# generic_maxi_speed_1.net
KiCad netlist of a schematic drawn in EAGLE
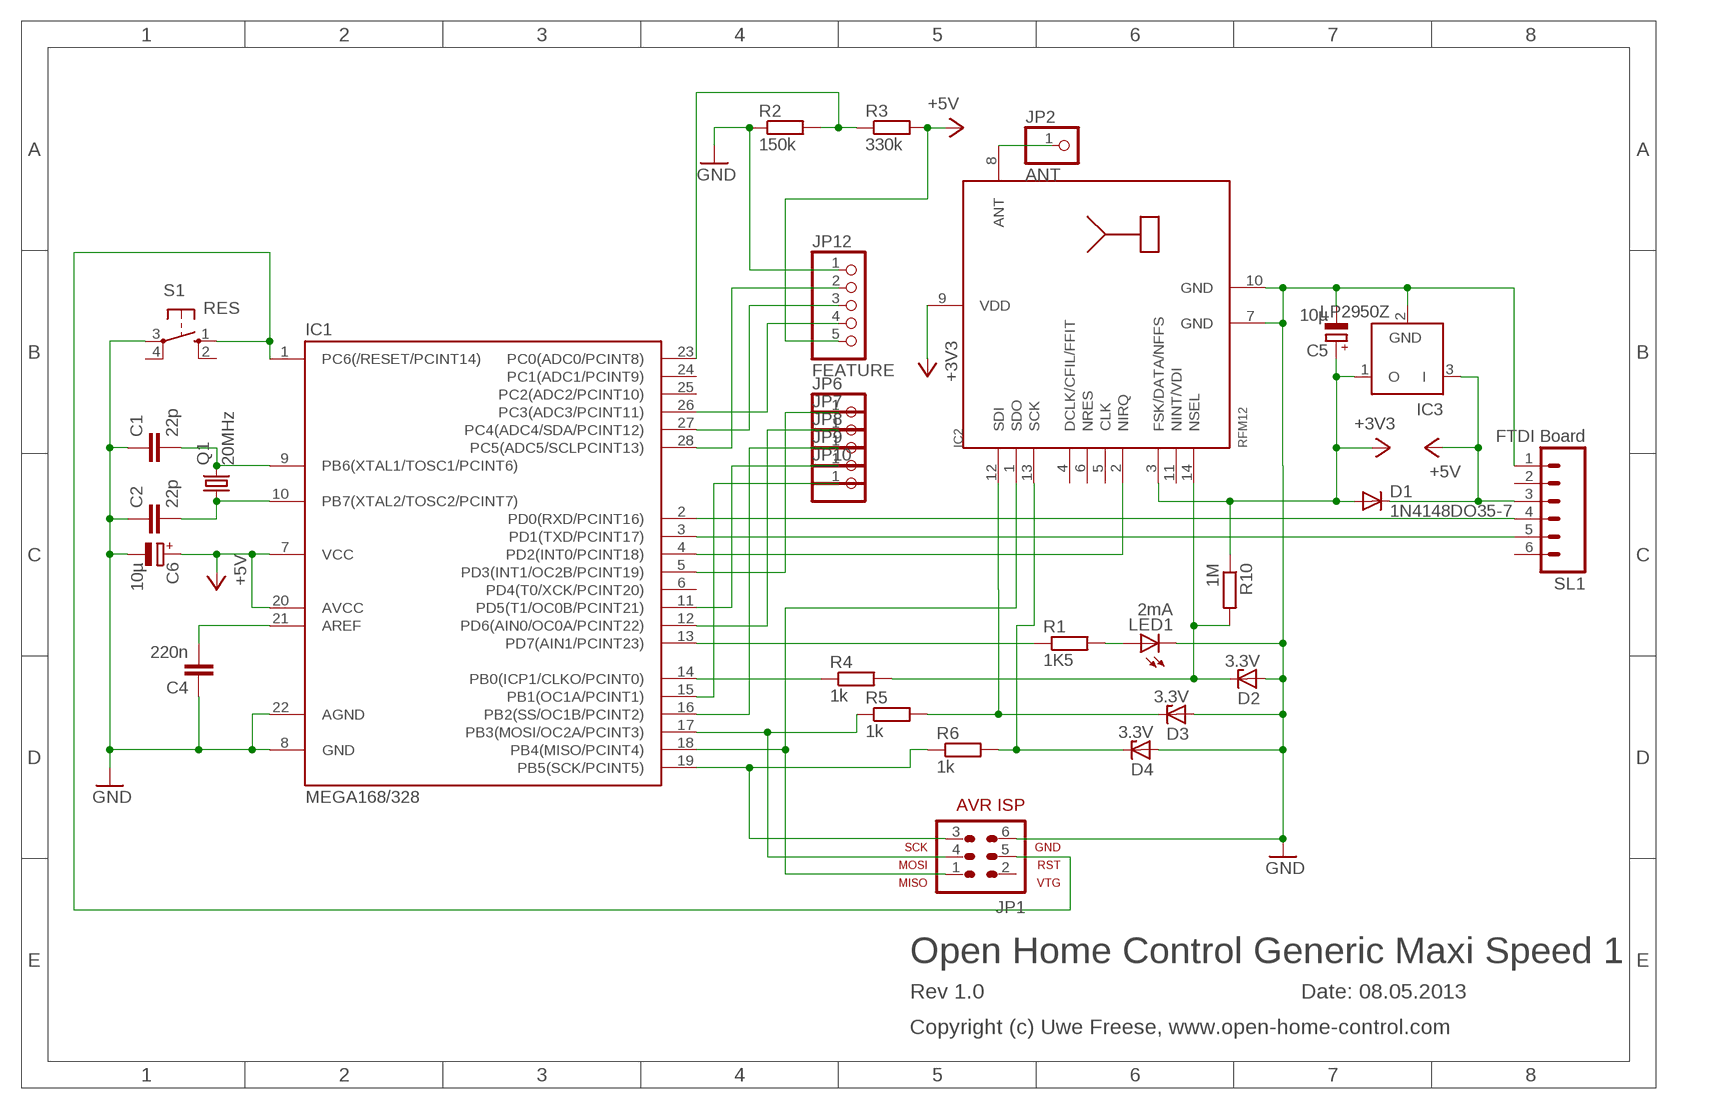
[diagram p0: schematic, sheet 1]

(export (version "E")
  (design (tool "Eeschema 10.0.6"))
  (components
    (comp (ref "C1")
      (value "22p")
      (footprint "eagle-import:C025-024X044")
      (libsource (lib "eagle-import") (part "C-EU025-024X044"))
    )
    (comp (ref "C2")
      (value "22p")
      (footprint "eagle-import:C025-024X044")
      (libsource (lib "eagle-import") (part "C-EU025-024X044"))
    )
    (comp (ref "C4")
      (value "220n")
      (footprint "eagle-import:C025-030X050")
      (libsource (lib "eagle-import") (part "C-EU025-030X050"))
    )
    (comp (ref "C5")
      (value "10µ")
      (footprint "eagle-import:E1,8-4")
      (libsource (lib "eagle-import") (part "CPOL-EUE1.8-4"))
    )
    (comp (ref "C6")
      (value "10µ")
      (footprint "eagle-import:E1,8-4")
      (libsource (lib "eagle-import") (part "CPOL-EUE1.8-4"))
    )
    (comp (ref "D1")
      (value "1N4148DO35-7")
      (footprint "eagle-import:DO35-7")
      (libsource (lib "eagle-import") (part "1N4148DO35-7"))
    )
    (comp (ref "D2")
      (value "3.3V")
      (footprint "eagle-import:ZDIO-5")
      (libsource (lib "eagle-import") (part "ZENER-DIODEZD-5"))
    )
    (comp (ref "D3")
      (value "3.3V")
      (footprint "eagle-import:ZDIO-5")
      (libsource (lib "eagle-import") (part "ZENER-DIODEZD-5"))
    )
    (comp (ref "D4")
      (value "3.3V")
      (footprint "eagle-import:ZDIO-5")
      (libsource (lib "eagle-import") (part "ZENER-DIODEZD-5"))
    )
    (comp (ref "IC1")
      (value "MEGA168/328")
      (footprint "eagle-import:DIL28-3")
      (libsource (lib "eagle-import") (part "MEGA48/88/168-PU"))
    )
    (comp (ref "IC2")
      (value "RFM12")
      (footprint "eagle-import:RFM")
      (libsource (lib "eagle-import") (part "RFM12"))
    )
    (comp (ref "IC3")
      (value "LP2950Z")
      (footprint "eagle-import:TO92")
      (libsource (lib "eagle-import") (part "LP2950Z"))
    )
    (comp (ref "JP1")
      (value "AVR-ISP-6")
      (footprint "eagle-import:AVR-ISP-6")
      (libsource (lib "eagle-import") (part "AVR-ISP-6"))
    )
    (comp (ref "JP2")
      (value "ANT")
      (footprint "eagle-import:1X01")
      (libsource (lib "eagle-import") (part "PINHD-1X1"))
    )
    (comp (ref "JP6")
      (value "PINHD-1X1")
      (footprint "eagle-import:1X01")
      (libsource (lib "eagle-import") (part "PINHD-1X1"))
    )
    (comp (ref "JP7")
      (value "PINHD-1X1")
      (footprint "eagle-import:1X01")
      (libsource (lib "eagle-import") (part "PINHD-1X1"))
    )
    (comp (ref "JP8")
      (value "PINHD-1X1")
      (footprint "eagle-import:1X01")
      (libsource (lib "eagle-import") (part "PINHD-1X1"))
    )
    (comp (ref "JP9")
      (value "PINHD-1X1")
      (footprint "eagle-import:1X01")
      (libsource (lib "eagle-import") (part "PINHD-1X1"))
    )
    (comp (ref "JP10")
      (value "PINHD-1X1")
      (footprint "eagle-import:1X01")
      (libsource (lib "eagle-import") (part "PINHD-1X1"))
    )
    (comp (ref "JP12")
      (value "FEATURE")
      (footprint "eagle-import:1X05")
      (libsource (lib "eagle-import") (part "PINHD-1X5"))
    )
    (comp (ref "LED1")
      (value "2mA")
      (footprint "eagle-import:LED3MM")
      (libsource (lib "eagle-import") (part "LED3MM"))
    )
    (comp (ref "Q1")
      (value "20MHz")
      (footprint "eagle-import:HC49_S")
      (libsource (lib "eagle-import") (part "CRYSTALHC49S"))
    )
    (comp (ref "R1")
      (value "1K5")
      (footprint "eagle-import:0207_7")
      (libsource (lib "eagle-import") (part "R-EU_0207/7"))
    )
    (comp (ref "R2")
      (value "150k")
      (footprint "eagle-import:0207_7")
      (libsource (lib "eagle-import") (part "R-EU_0207/7"))
    )
    (comp (ref "R3")
      (value "330k")
      (footprint "eagle-import:0207_7")
      (libsource (lib "eagle-import") (part "R-EU_0207/7"))
    )
    (comp (ref "R4")
      (value "1k")
      (footprint "eagle-import:0207_7")
      (libsource (lib "eagle-import") (part "R-EU_0207/7"))
    )
    (comp (ref "R5")
      (value "1k")
      (footprint "eagle-import:0207_7")
      (libsource (lib "eagle-import") (part "R-EU_0207/7"))
    )
    (comp (ref "R6")
      (value "1k")
      (footprint "eagle-import:0207_7")
      (libsource (lib "eagle-import") (part "R-EU_0207/7"))
    )
    (comp (ref "R10")
      (value "1M")
      (footprint "eagle-import:0207_7")
      (libsource (lib "eagle-import") (part "R-EU_0207/7"))
    )
    (comp (ref "S1")
      (value "RES")
      (footprint "eagle-import:B3F-10XX")
      (fields (field (name "MPN") "B3F-1000"))
      (libsource (lib "eagle-import") (part "10-XX"))
    )
    (comp (ref "SL1")
      (value "FTDI Board")
      (footprint "eagle-import:06P")
      (libsource (lib "eagle-import") (part "M06"))
    )
  )
  (nets
    (net (code "1") (name "+3V3") (class "Default")
      (node (ref "C5") (pin "+") (pinfunction "+_+") (pintype "passive"))
      (node (ref "D1") (pin "A") (pinfunction "A_A") (pintype "passive"))
      (node (ref "IC2") (pin "3") (pinfunction "FSK/DATA/NFFS_3") (pintype "bidirectional"))
      (node (ref "IC2") (pin "9") (pinfunction "VDD_9") (pintype "power_in"))
      (node (ref "IC3") (pin "1") (pinfunction "O_1") (pintype "input"))
      (node (ref "R10") (pin "1") (pinfunction "1_1") (pintype "passive"))
    )
    (net (code "2") (name "+5V") (class "Default")
      (node (ref "C6") (pin "+") (pinfunction "+_+") (pintype "passive"))
      (node (ref "D1") (pin "C") (pinfunction "C_C") (pintype "passive"))
      (node (ref "IC1") (pin "20") (pinfunction "AVCC_20") (pintype "passive"))
      (node (ref "IC1") (pin "7") (pinfunction "VCC_7") (pintype "power_in"))
      (node (ref "IC3") (pin "3") (pinfunction "I_3") (pintype "input"))
      (node (ref "JP12") (pin "5") (pinfunction "5_5") (pintype "passive"))
      (node (ref "R3") (pin "2") (pinfunction "2_2") (pintype "passive"))
      (node (ref "SL1") (pin "3") (pinfunction "3_3") (pintype "passive"))
    )
    (net (code "3") (name "GND") (class "Default")
      (node (ref "C1") (pin "1") (pinfunction "1_1") (pintype "passive"))
      (node (ref "C2") (pin "1") (pinfunction "1_1") (pintype "passive"))
      (node (ref "C4") (pin "1") (pinfunction "1_1") (pintype "passive"))
      (node (ref "C5") (pin "-") (pinfunction "-_-") (pintype "passive"))
      (node (ref "C6") (pin "-") (pinfunction "-_-") (pintype "passive"))
      (node (ref "D2") (pin "A") (pinfunction "A_A") (pintype "passive"))
      (node (ref "D3") (pin "A") (pinfunction "A_A") (pintype "passive"))
      (node (ref "D4") (pin "A") (pinfunction "A_A") (pintype "passive"))
      (node (ref "IC1") (pin "22") (pinfunction "AGND_22") (pintype "power_in"))
      (node (ref "IC1") (pin "8") (pinfunction "GND_8") (pintype "power_in"))
      (node (ref "IC2") (pin "10") (pinfunction "GND_10") (pintype "power_in"))
      (node (ref "IC2") (pin "7") (pinfunction "GND_7") (pintype "power_in"))
      (node (ref "IC3") (pin "2") (pinfunction "GND_2") (pintype "power_in"))
      (node (ref "JP1") (pin "6") (pinfunction "6_6") (pintype "passive"))
      (node (ref "JP12") (pin "1") (pinfunction "1_1") (pintype "passive"))
      (node (ref "LED1") (pin "K") (pinfunction "C_K") (pintype "passive"))
      (node (ref "R2") (pin "1") (pinfunction "1_1") (pintype "passive"))
      (node (ref "S1") (pin "3") (pinfunction "P_3") (pintype "passive"))
      (node (ref "SL1") (pin "1") (pinfunction "1_1") (pintype "passive"))
    )
    (net (code "4") (name "Net-(IC1-AREF)") (class "Default")
      (node (ref "C4") (pin "2") (pinfunction "2_2") (pintype "passive"))
      (node (ref "IC1") (pin "21") (pinfunction "AREF_21") (pintype "passive"))
    )
    (net (code "5") (name "Net-(IC1-PB0(ICP1{slash}CLKO{slash}PCINT0))") (class "Default")
      (node (ref "IC1") (pin "14") (pinfunction "PB0(ICP1/CLKO/PCINT0)_14") (pintype "bidirectional"))
      (node (ref "R4") (pin "1") (pinfunction "1_1") (pintype "passive"))
    )
    (net (code "6") (name "Net-(IC1-PB1(OC1A{slash}PCINT1))") (class "Default")
      (node (ref "IC1") (pin "15") (pinfunction "PB1(OC1A/PCINT1)_15") (pintype "bidirectional"))
      (node (ref "JP10") (pin "1") (pinfunction "1_1") (pintype "passive"))
    )
    (net (code "7") (name "Net-(IC1-PB2(SS{slash}OC1B{slash}PCINT2))") (class "Default")
      (node (ref "IC1") (pin "16") (pinfunction "PB2(SS/OC1B/PCINT2)_16") (pintype "bidirectional"))
      (node (ref "JP8") (pin "1") (pinfunction "1_1") (pintype "passive"))
    )
    (net (code "8") (name "Net-(IC1-PB3(MOSI{slash}OC2A{slash}PCINT3))") (class "Default")
      (node (ref "IC1") (pin "17") (pinfunction "PB3(MOSI/OC2A/PCINT3)_17") (pintype "bidirectional"))
      (node (ref "JP1") (pin "4") (pinfunction "4_4") (pintype "passive"))
      (node (ref "R5") (pin "1") (pinfunction "1_1") (pintype "passive"))
    )
    (net (code "9") (name "Net-(IC1-PB4(MISO{slash}PCINT4))") (class "Default")
      (node (ref "IC1") (pin "18") (pinfunction "PB4(MISO/PCINT4)_18") (pintype "bidirectional"))
      (node (ref "IC2") (pin "1") (pinfunction "SDO_1") (pintype "bidirectional"))
      (node (ref "JP1") (pin "1") (pinfunction "1_1") (pintype "passive"))
    )
    (net (code "10") (name "Net-(IC1-PB5(SCK{slash}PCINT5))") (class "Default")
      (node (ref "IC1") (pin "19") (pinfunction "PB5(SCK/PCINT5)_19") (pintype "bidirectional"))
      (node (ref "JP1") (pin "3") (pinfunction "3_3") (pintype "passive"))
      (node (ref "R6") (pin "1") (pinfunction "1_1") (pintype "passive"))
    )
    (net (code "11") (name "Net-(IC1-PB6(XTAL1{slash}TOSC1{slash}PCINT6))") (class "Default")
      (node (ref "C1") (pin "2") (pinfunction "2_2") (pintype "passive"))
      (node (ref "IC1") (pin "9") (pinfunction "PB6(XTAL1/TOSC1/PCINT6)_9") (pintype "bidirectional"))
      (node (ref "Q1") (pin "2") (pinfunction "2_2") (pintype "passive"))
    )
    (net (code "12") (name "Net-(IC1-PB7(XTAL2{slash}TOSC2{slash}PCINT7))") (class "Default")
      (node (ref "C2") (pin "2") (pinfunction "2_2") (pintype "passive"))
      (node (ref "IC1") (pin "10") (pinfunction "PB7(XTAL2/TOSC2/PCINT7)_10") (pintype "bidirectional"))
      (node (ref "Q1") (pin "1") (pinfunction "1_1") (pintype "passive"))
    )
    (net (code "13") (name "Net-(IC1-PC0(ADC0{slash}PCINT8))") (class "Default")
      (node (ref "IC1") (pin "23") (pinfunction "PC0(ADC0/PCINT8)_23") (pintype "bidirectional"))
      (node (ref "R2") (pin "2") (pinfunction "2_2") (pintype "passive"))
      (node (ref "R3") (pin "1") (pinfunction "1_1") (pintype "passive"))
    )
    (net (code "14") (name "Net-(IC1-PC3(ADC3{slash}PCINT11))") (class "Default")
      (node (ref "IC1") (pin "26") (pinfunction "PC3(ADC3/PCINT11)_26") (pintype "bidirectional"))
      (node (ref "JP12") (pin "4") (pinfunction "4_4") (pintype "passive"))
    )
    (net (code "15") (name "Net-(IC1-PC4(ADC4{slash}SDA{slash}PCINT12))") (class "Default")
      (node (ref "IC1") (pin "27") (pinfunction "PC4(ADC4/SDA/PCINT12)_27") (pintype "bidirectional"))
      (node (ref "JP12") (pin "3") (pinfunction "3_3") (pintype "passive"))
    )
    (net (code "16") (name "Net-(IC1-PC5(ADC5{slash}SCLPCINT13))") (class "Default")
      (node (ref "IC1") (pin "28") (pinfunction "PC5(ADC5/SCLPCINT13)_28") (pintype "bidirectional"))
      (node (ref "JP12") (pin "2") (pinfunction "2_2") (pintype "passive"))
    )
    (net (code "17") (name "Net-(IC1-PC6({slash}RESET{slash}PCINT14))") (class "Default")
      (node (ref "IC1") (pin "1") (pinfunction "PC6(/RESET/PCINT14)_1") (pintype "bidirectional"))
      (node (ref "JP1") (pin "5") (pinfunction "5_5") (pintype "passive"))
      (node (ref "S1") (pin "1") (pinfunction "S_1") (pintype "passive"))
    )
    (net (code "18") (name "Net-(IC1-PD0(RXD{slash}PCINT16))") (class "Default")
      (node (ref "IC1") (pin "2") (pinfunction "PD0(RXD/PCINT16)_2") (pintype "bidirectional"))
      (node (ref "SL1") (pin "4") (pinfunction "4_4") (pintype "passive"))
    )
    (net (code "19") (name "Net-(IC1-PD1(TXD{slash}PCINT17))") (class "Default")
      (node (ref "IC1") (pin "3") (pinfunction "PD1(TXD/PCINT17)_3") (pintype "bidirectional"))
      (node (ref "SL1") (pin "5") (pinfunction "5_5") (pintype "passive"))
    )
    (net (code "20") (name "Net-(IC1-PD2(INT0{slash}PCINT18))") (class "Default")
      (node (ref "IC1") (pin "4") (pinfunction "PD2(INT0/PCINT18)_4") (pintype "bidirectional"))
      (node (ref "IC2") (pin "2") (pinfunction "NIRQ_2") (pintype "bidirectional"))
    )
    (net (code "21") (name "Net-(IC1-PD3(INT1{slash}OC2B{slash}PCINT19))") (class "Default")
      (node (ref "IC1") (pin "5") (pinfunction "PD3(INT1/OC2B/PCINT19)_5") (pintype "bidirectional"))
      (node (ref "JP6") (pin "1") (pinfunction "1_1") (pintype "passive"))
    )
    (net (code "22") (name "Net-(IC1-PD5(T1{slash}OC0B{slash}PCINT21))") (class "Default")
      (node (ref "IC1") (pin "11") (pinfunction "PD5(T1/OC0B/PCINT21)_11") (pintype "bidirectional"))
      (node (ref "JP9") (pin "1") (pinfunction "1_1") (pintype "passive"))
    )
    (net (code "23") (name "Net-(IC1-PD6(AIN0{slash}OC0A{slash}PCINT22))") (class "Default")
      (node (ref "IC1") (pin "12") (pinfunction "PD6(AIN0/OC0A/PCINT22)_12") (pintype "bidirectional"))
      (node (ref "JP7") (pin "1") (pinfunction "1_1") (pintype "passive"))
    )
    (net (code "24") (name "Net-(IC1-PD7(AIN1{slash}PCINT23))") (class "Default")
      (node (ref "IC1") (pin "13") (pinfunction "PD7(AIN1/PCINT23)_13") (pintype "bidirectional"))
      (node (ref "R1") (pin "1") (pinfunction "1_1") (pintype "passive"))
    )
    (net (code "25") (name "Net-(IC2-ANT)") (class "Default")
      (node (ref "IC2") (pin "8") (pinfunction "ANT_8") (pintype "output"))
      (node (ref "JP2") (pin "1") (pinfunction "1_1") (pintype "passive"))
    )
    (net (code "26") (name "Net-(IC2-NSEL)") (class "Default")
      (node (ref "D2") (pin "C") (pinfunction "C_C") (pintype "passive"))
      (node (ref "IC2") (pin "14") (pinfunction "NSEL_14") (pintype "bidirectional"))
      (node (ref "R10") (pin "2") (pinfunction "2_2") (pintype "passive"))
      (node (ref "R4") (pin "2") (pinfunction "2_2") (pintype "passive"))
    )
    (net (code "27") (name "Net-(IC2-SCK)") (class "Default")
      (node (ref "D4") (pin "C") (pinfunction "C_C") (pintype "passive"))
      (node (ref "IC2") (pin "13") (pinfunction "SCK_13") (pintype "bidirectional"))
      (node (ref "R6") (pin "2") (pinfunction "2_2") (pintype "passive"))
    )
    (net (code "28") (name "Net-(IC2-SDI)") (class "Default")
      (node (ref "D3") (pin "C") (pinfunction "C_C") (pintype "passive"))
      (node (ref "IC2") (pin "12") (pinfunction "SDI_12") (pintype "bidirectional"))
      (node (ref "R5") (pin "2") (pinfunction "2_2") (pintype "passive"))
    )
    (net (code "29") (name "Net-(LED1-PadA)") (class "Default")
      (node (ref "LED1") (pin "A") (pinfunction "A_A") (pintype "passive"))
      (node (ref "R1") (pin "2") (pinfunction "2_2") (pintype "passive"))
    )
    (net (code "30") (name "unconnected-(IC1-PC1(ADC1{slash}PCINT9)-Pad24)") (class "Default")
      (node (ref "IC1") (pin "24") (pinfunction "PC1(ADC1/PCINT9)_24") (pintype "bidirectional"))
    )
    (net (code "31") (name "unconnected-(IC1-PC2(ADC2{slash}PCINT10)-Pad25)") (class "Default")
      (node (ref "IC1") (pin "25") (pinfunction "PC2(ADC2/PCINT10)_25") (pintype "bidirectional"))
    )
    (net (code "32") (name "unconnected-(IC1-PD4(T0{slash}XCK{slash}PCINT20)-Pad6)") (class "Default")
      (node (ref "IC1") (pin "6") (pinfunction "PD4(T0/XCK/PCINT20)_6") (pintype "bidirectional"))
    )
    (net (code "33") (name "unconnected-(IC2-CLK-Pad5)") (class "Default")
      (node (ref "IC2") (pin "5") (pinfunction "CLK_5") (pintype "bidirectional"))
    )
    (net (code "34") (name "unconnected-(IC2-DCLK{slash}CFIL{slash}FFIT-Pad4)") (class "Default")
      (node (ref "IC2") (pin "4") (pinfunction "DCLK/CFIL/FFIT_4") (pintype "bidirectional"))
    )
    (net (code "35") (name "unconnected-(IC2-NINT{slash}VDI-Pad11)") (class "Default")
      (node (ref "IC2") (pin "11") (pinfunction "NINT/VDI_11") (pintype "bidirectional"))
    )
    (net (code "36") (name "unconnected-(IC2-NRES-Pad6)") (class "Default")
      (node (ref "IC2") (pin "6") (pinfunction "NRES_6") (pintype "bidirectional"))
    )
    (net (code "37") (name "unconnected-(JP1-Pad2)") (class "Default")
      (node (ref "JP1") (pin "2") (pinfunction "2_2") (pintype "passive"))
    )
    (net (code "38") (name "unconnected-(S1-P1-Pad4)") (class "Default")
      (node (ref "S1") (pin "4") (pinfunction "P1_4") (pintype "passive"))
    )
    (net (code "39") (name "unconnected-(S1-S1-Pad2)") (class "Default")
      (node (ref "S1") (pin "2") (pinfunction "S1_2") (pintype "passive"))
    )
    (net (code "40") (name "unconnected-(SL1-Pad2)") (class "Default")
      (node (ref "SL1") (pin "2") (pinfunction "2_2") (pintype "passive"))
    )
    (net (code "41") (name "unconnected-(SL1-Pad6)") (class "Default")
      (node (ref "SL1") (pin "6") (pinfunction "6_6") (pintype "passive"))
    )
  )
)
